# s340k.net
KiCad netlist of a schematic drawn in EAGLE
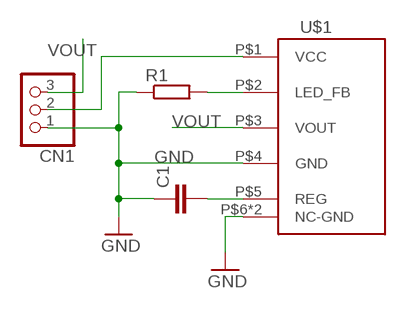
[diagram p0: schematic, sheet 1]

(export (version "E")
  (design (tool "Eeschema 10.0.6"))
  (components
    (comp (ref "C1")
      (value "C-EUC0805")
      (footprint "eagle-import:C0805")
      (libsource (lib "eagle-import") (part "C-EUC0805"))
    )
    (comp (ref "CN1")
      (value "JST_3PIN")
      (footprint "eagle-import:JSTPH3")
      (libsource (lib "eagle-import") (part "JST_3PIN"))
    )
    (comp (ref "R1")
      (value "R-EU_R1206")
      (footprint "eagle-import:R1206")
      (libsource (lib "eagle-import") (part "R-EU_R1206"))
    )
    (comp (ref "U$1")
      (value "340K")
      (footprint "eagle-import:SHARP_340K")
      (libsource (lib "eagle-import") (part "340K"))
    )
  )
  (nets
    (net (code "1") (name "/VOUT") (class "Default")
      (node (ref "CN1") (pin "3") (pinfunction "3_3") (pintype "passive"))
      (node (ref "U$1") (pin "P$3") (pinfunction "VOUT_P$3") (pintype "bidirectional"))
    )
    (net (code "2") (name "GND") (class "Default")
      (node (ref "C1") (pin "1") (pinfunction "1_1") (pintype "passive"))
      (node (ref "CN1") (pin "1") (pinfunction "1_1") (pintype "passive"))
      (node (ref "R1") (pin "1") (pinfunction "1_1") (pintype "passive"))
      (node (ref "U$1") (pin "P$4") (pinfunction "GND_P$4") (pintype "bidirectional"))
      (node (ref "U$1") (pin "P$6") (pinfunction "NC-GND_P$6") (pintype "bidirectional"))
      (node (ref "U$1") (pin "P$7") (pinfunction "NC-GND_P$7") (pintype "bidirectional"))
    )
    (net (code "3") (name "Net-(U$1-LED_FB)") (class "Default")
      (node (ref "R1") (pin "2") (pinfunction "2_2") (pintype "passive"))
      (node (ref "U$1") (pin "P$2") (pinfunction "LED_FB_P$2") (pintype "bidirectional"))
    )
    (net (code "4") (name "Net-(U$1-REG)") (class "Default")
      (node (ref "C1") (pin "2") (pinfunction "2_2") (pintype "passive"))
      (node (ref "U$1") (pin "P$5") (pinfunction "REG_P$5") (pintype "bidirectional"))
    )
    (net (code "5") (name "Net-(U$1-VCC)") (class "Default")
      (node (ref "CN1") (pin "2") (pinfunction "2_2") (pintype "passive"))
      (node (ref "U$1") (pin "P$1") (pinfunction "VCC_P$1") (pintype "bidirectional"))
    )
  )
)
